# main.net
KiCad netlist of a schematic drawn in Altium Designer
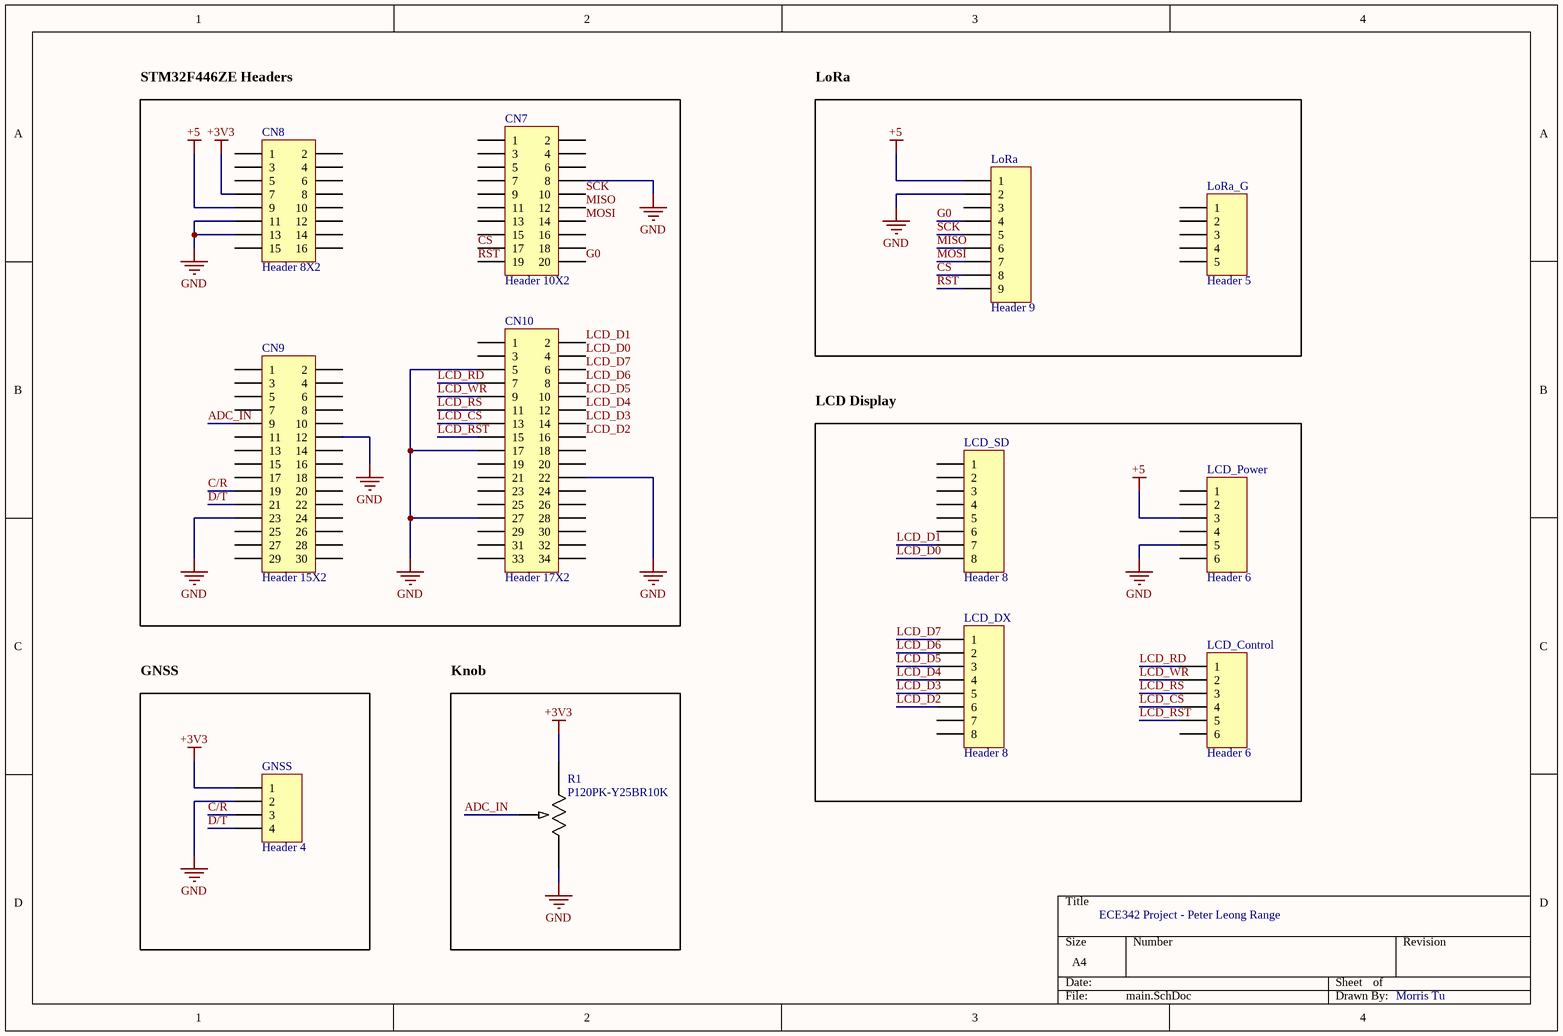
[diagram p0: main.SchDoc]

(export (version "E")
  (design (tool "Eeschema 10.0.6"))
  (components
    (comp (ref "CN7")
      (value "Header 10X2")
      (footprint "HDR2X10")
      (description "Header, 10-Pin, Dual row")
      (fields (field (name "PUBLISHER") "Altium Limited"))
      (libsource (lib "Miscellaneous Connectors") (part "Header 10X2"))
    )
    (comp (ref "CN8")
      (value "Header 8X2")
      (footprint "HDR2X8")
      (description "Header, 8-Pin, Dual row")
      (fields (field (name "PUBLISHER") "Altium Limited"))
      (libsource (lib "Miscellaneous Connectors") (part "Header 8X2"))
    )
    (comp (ref "CN9")
      (value "Header 15X2")
      (footprint "HDR2X15")
      (description "Header, 15-Pin, Dual row")
      (fields (field (name "PUBLISHER") "Altium Limited"))
      (libsource (lib "Miscellaneous Connectors") (part "Header 15X2"))
    )
    (comp (ref "CN10")
      (value "Header 17X2")
      (footprint "HDR2X17")
      (description "Header, 17-Pin, Dual row")
      (fields (field (name "PUBLISHER") "Altium Limited"))
      (libsource (lib "Miscellaneous Connectors") (part "Header 17X2"))
    )
    (comp (ref "GNSS")
      (value "Header 4")
      (footprint "HDR1X4")
      (description "Header, 4-Pin")
      (fields (field (name "PUBLISHER") "Altium Limited"))
      (libsource (lib "Miscellaneous Connectors") (part "Header 4"))
    )
    (comp (ref "LCD_Control")
      (value "Header 6")
      (footprint "HDR1X6")
      (description "Header, 6-Pin")
      (fields (field (name "PUBLISHER") "Altium Limited"))
      (libsource (lib "Miscellaneous Connectors") (part "Header 6"))
    )
    (comp (ref "LCD_DX")
      (value "Header 8")
      (footprint "HDR1X8")
      (description "Header, 8-Pin")
      (fields (field (name "PUBLISHER") "Altium Limited"))
      (libsource (lib "Miscellaneous Connectors") (part "Header 8"))
    )
    (comp (ref "LCD_Power")
      (value "Header 6")
      (footprint "HDR1X6")
      (description "Header, 6-Pin")
      (fields (field (name "PUBLISHER") "Altium Limited"))
      (libsource (lib "Miscellaneous Connectors") (part "Header 6"))
    )
    (comp (ref "LCD_SD")
      (value "Header 8")
      (footprint "HDR1X8")
      (description "Header, 8-Pin")
      (fields (field (name "PUBLISHER") "Altium Limited"))
      (libsource (lib "Miscellaneous Connectors") (part "Header 8"))
    )
    (comp (ref "LoRa")
      (value "Header 9")
      (footprint "HDR1X9")
      (description "Header, 9-Pin")
      (fields (field (name "PUBLISHER") "Altium Limited"))
      (libsource (lib "Miscellaneous Connectors") (part "Header 9"))
    )
    (comp (ref "LoRa_G")
      (value "Header 5")
      (footprint "HDR1X5")
      (description "Header, 5-Pin")
      (fields (field (name "PUBLISHER") "Altium Limited"))
      (libsource (lib "Miscellaneous Connectors") (part "Header 5"))
    )
    (comp (ref "R1")
      (value "P120PK-Y25BR10K")
      (footprint "POT_P120PK-x25_TTE")
      (description "Description")
      (fields (field (name "COPYRIGHT") "Copyright (C) 2025 Ultra Librarian. All rights reserved."))
      (libsource (lib "P120PK-Y25BR10K") (part "P120PK-Y25BR10K"))
    )
  )
  (nets
    (net (code "1") (name "+3V3") (class "Default")
      (node (ref "CN8") (pin "7") (pinfunction "7_7") (pintype "passive"))
      (node (ref "GNSS") (pin "1") (pinfunction "1_1") (pintype "passive"))
      (node (ref "R1") (pin "3") (pinfunction "3_3") (pintype "passive"))
    )
    (net (code "2") (name "+5") (class "Default")
      (node (ref "CN8") (pin "9") (pinfunction "9_9") (pintype "passive"))
      (node (ref "LCD_Power") (pin "3") (pinfunction "3_3") (pintype "passive"))
      (node (ref "LoRa") (pin "1") (pinfunction "1_1") (pintype "passive"))
    )
    (net (code "3") (name "/ADC_IN") (class "Default")
      (node (ref "CN9") (pin "9") (pinfunction "9_9") (pintype "passive"))
      (node (ref "R1") (pin "2") (pinfunction "2_2") (pintype "passive"))
    )
    (net (code "4") (name "/CS") (class "Default")
      (node (ref "CN7") (pin "17") (pinfunction "17_17") (pintype "passive"))
      (node (ref "LoRa") (pin "8") (pinfunction "8_8") (pintype "passive"))
    )
    (net (code "5") (name "/C{slash}R") (class "Default")
      (node (ref "CN9") (pin "19") (pinfunction "19_19") (pintype "passive"))
      (node (ref "GNSS") (pin "3") (pinfunction "3_3") (pintype "passive"))
    )
    (net (code "6") (name "/D{slash}T") (class "Default")
      (node (ref "CN9") (pin "21") (pinfunction "21_21") (pintype "passive"))
      (node (ref "GNSS") (pin "4") (pinfunction "4_4") (pintype "passive"))
    )
    (net (code "7") (name "/G0") (class "Default")
      (node (ref "CN7") (pin "20") (pinfunction "20_20") (pintype "passive"))
      (node (ref "LoRa") (pin "4") (pinfunction "4_4") (pintype "passive"))
    )
    (net (code "8") (name "/LCD_CS") (class "Default")
      (node (ref "CN10") (pin "13") (pinfunction "13_13") (pintype "passive"))
      (node (ref "LCD_Control") (pin "4") (pinfunction "4_4") (pintype "passive"))
    )
    (net (code "9") (name "/LCD_D0") (class "Default")
      (node (ref "CN10") (pin "4") (pinfunction "4_4") (pintype "passive"))
      (node (ref "LCD_SD") (pin "8") (pinfunction "8_8") (pintype "passive"))
    )
    (net (code "10") (name "/LCD_D1") (class "Default")
      (node (ref "CN10") (pin "2") (pinfunction "2_2") (pintype "passive"))
      (node (ref "LCD_SD") (pin "7") (pinfunction "7_7") (pintype "passive"))
    )
    (net (code "11") (name "/LCD_D2") (class "Default")
      (node (ref "CN10") (pin "16") (pinfunction "16_16") (pintype "passive"))
      (node (ref "LCD_DX") (pin "6") (pinfunction "6_6") (pintype "passive"))
    )
    (net (code "12") (name "/LCD_D3") (class "Default")
      (node (ref "CN10") (pin "14") (pinfunction "14_14") (pintype "passive"))
      (node (ref "LCD_DX") (pin "5") (pinfunction "5_5") (pintype "passive"))
    )
    (net (code "13") (name "/LCD_D4") (class "Default")
      (node (ref "CN10") (pin "12") (pinfunction "12_12") (pintype "passive"))
      (node (ref "LCD_DX") (pin "4") (pinfunction "4_4") (pintype "passive"))
    )
    (net (code "14") (name "/LCD_D5") (class "Default")
      (node (ref "CN10") (pin "10") (pinfunction "10_10") (pintype "passive"))
      (node (ref "LCD_DX") (pin "3") (pinfunction "3_3") (pintype "passive"))
    )
    (net (code "15") (name "/LCD_D6") (class "Default")
      (node (ref "CN10") (pin "8") (pinfunction "8_8") (pintype "passive"))
      (node (ref "LCD_DX") (pin "2") (pinfunction "2_2") (pintype "passive"))
    )
    (net (code "16") (name "/LCD_D7") (class "Default")
      (node (ref "CN10") (pin "6") (pinfunction "6_6") (pintype "passive"))
      (node (ref "LCD_DX") (pin "1") (pinfunction "1_1") (pintype "passive"))
    )
    (net (code "17") (name "/LCD_RD") (class "Default")
      (node (ref "CN10") (pin "7") (pinfunction "7_7") (pintype "passive"))
      (node (ref "LCD_Control") (pin "1") (pinfunction "1_1") (pintype "passive"))
    )
    (net (code "18") (name "/LCD_RS") (class "Default")
      (node (ref "CN10") (pin "11") (pinfunction "11_11") (pintype "passive"))
      (node (ref "LCD_Control") (pin "3") (pinfunction "3_3") (pintype "passive"))
    )
    (net (code "19") (name "/LCD_RST") (class "Default")
      (node (ref "CN10") (pin "15") (pinfunction "15_15") (pintype "passive"))
      (node (ref "LCD_Control") (pin "5") (pinfunction "5_5") (pintype "passive"))
    )
    (net (code "20") (name "/LCD_WR") (class "Default")
      (node (ref "CN10") (pin "9") (pinfunction "9_9") (pintype "passive"))
      (node (ref "LCD_Control") (pin "2") (pinfunction "2_2") (pintype "passive"))
    )
    (net (code "21") (name "/MISO") (class "Default")
      (node (ref "CN7") (pin "12") (pinfunction "12_12") (pintype "passive"))
      (node (ref "LoRa") (pin "6") (pinfunction "6_6") (pintype "passive"))
    )
    (net (code "22") (name "/MOSI") (class "Default")
      (node (ref "CN7") (pin "14") (pinfunction "14_14") (pintype "passive"))
      (node (ref "LoRa") (pin "7") (pinfunction "7_7") (pintype "passive"))
    )
    (net (code "23") (name "/RST") (class "Default")
      (node (ref "CN7") (pin "19") (pinfunction "19_19") (pintype "passive"))
      (node (ref "LoRa") (pin "9") (pinfunction "9_9") (pintype "passive"))
    )
    (net (code "24") (name "/SCK") (class "Default")
      (node (ref "CN7") (pin "10") (pinfunction "10_10") (pintype "passive"))
      (node (ref "LoRa") (pin "5") (pinfunction "5_5") (pintype "passive"))
    )
    (net (code "25") (name "GND") (class "Default")
      (node (ref "CN10") (pin "17") (pinfunction "17_17") (pintype "passive"))
      (node (ref "CN10") (pin "22") (pinfunction "22_22") (pintype "passive"))
      (node (ref "CN10") (pin "27") (pinfunction "27_27") (pintype "passive"))
      (node (ref "CN10") (pin "5") (pinfunction "5_5") (pintype "passive"))
      (node (ref "CN7") (pin "8") (pinfunction "8_8") (pintype "passive"))
      (node (ref "CN8") (pin "11") (pinfunction "11_11") (pintype "passive"))
      (node (ref "CN8") (pin "13") (pinfunction "13_13") (pintype "passive"))
      (node (ref "CN9") (pin "12") (pinfunction "12_12") (pintype "passive"))
      (node (ref "CN9") (pin "23") (pinfunction "23_23") (pintype "passive"))
      (node (ref "GNSS") (pin "2") (pinfunction "2_2") (pintype "passive"))
      (node (ref "LCD_Power") (pin "5") (pinfunction "5_5") (pintype "passive"))
      (node (ref "LoRa") (pin "2") (pinfunction "2_2") (pintype "passive"))
      (node (ref "R1") (pin "1") (pinfunction "1_1") (pintype "passive"))
    )
    (net (code "26") (name "unconnected-(CN7-Pad1)") (class "Default")
      (node (ref "CN7") (pin "1") (pinfunction "1_1") (pintype "passive"))
    )
    (net (code "27") (name "unconnected-(CN7-Pad2)") (class "Default")
      (node (ref "CN7") (pin "2") (pinfunction "2_2") (pintype "passive"))
    )
    (net (code "28") (name "unconnected-(CN7-Pad3)") (class "Default")
      (node (ref "CN7") (pin "3") (pinfunction "3_3") (pintype "passive"))
    )
    (net (code "29") (name "unconnected-(CN7-Pad4)") (class "Default")
      (node (ref "CN7") (pin "4") (pinfunction "4_4") (pintype "passive"))
    )
    (net (code "30") (name "unconnected-(CN7-Pad5)") (class "Default")
      (node (ref "CN7") (pin "5") (pinfunction "5_5") (pintype "passive"))
    )
    (net (code "31") (name "unconnected-(CN7-Pad6)") (class "Default")
      (node (ref "CN7") (pin "6") (pinfunction "6_6") (pintype "passive"))
    )
    (net (code "32") (name "unconnected-(CN7-Pad7)") (class "Default")
      (node (ref "CN7") (pin "7") (pinfunction "7_7") (pintype "passive"))
    )
    (net (code "33") (name "unconnected-(CN7-Pad9)") (class "Default")
      (node (ref "CN7") (pin "9") (pinfunction "9_9") (pintype "passive"))
    )
    (net (code "34") (name "unconnected-(CN7-Pad11)") (class "Default")
      (node (ref "CN7") (pin "11") (pinfunction "11_11") (pintype "passive"))
    )
    (net (code "35") (name "unconnected-(CN7-Pad13)") (class "Default")
      (node (ref "CN7") (pin "13") (pinfunction "13_13") (pintype "passive"))
    )
    (net (code "36") (name "unconnected-(CN7-Pad15)") (class "Default")
      (node (ref "CN7") (pin "15") (pinfunction "15_15") (pintype "passive"))
    )
    (net (code "37") (name "unconnected-(CN7-Pad16)") (class "Default")
      (node (ref "CN7") (pin "16") (pinfunction "16_16") (pintype "passive"))
    )
    (net (code "38") (name "unconnected-(CN7-Pad18)") (class "Default")
      (node (ref "CN7") (pin "18") (pinfunction "18_18") (pintype "passive"))
    )
    (net (code "39") (name "unconnected-(CN8-Pad1)") (class "Default")
      (node (ref "CN8") (pin "1") (pinfunction "1_1") (pintype "passive"))
    )
    (net (code "40") (name "unconnected-(CN8-Pad2)") (class "Default")
      (node (ref "CN8") (pin "2") (pinfunction "2_2") (pintype "passive"))
    )
    (net (code "41") (name "unconnected-(CN8-Pad3)") (class "Default")
      (node (ref "CN8") (pin "3") (pinfunction "3_3") (pintype "passive"))
    )
    (net (code "42") (name "unconnected-(CN8-Pad4)") (class "Default")
      (node (ref "CN8") (pin "4") (pinfunction "4_4") (pintype "passive"))
    )
    (net (code "43") (name "unconnected-(CN8-Pad5)") (class "Default")
      (node (ref "CN8") (pin "5") (pinfunction "5_5") (pintype "passive"))
    )
    (net (code "44") (name "unconnected-(CN8-Pad6)") (class "Default")
      (node (ref "CN8") (pin "6") (pinfunction "6_6") (pintype "passive"))
    )
    (net (code "45") (name "unconnected-(CN8-Pad8)") (class "Default")
      (node (ref "CN8") (pin "8") (pinfunction "8_8") (pintype "passive"))
    )
    (net (code "46") (name "unconnected-(CN8-Pad10)") (class "Default")
      (node (ref "CN8") (pin "10") (pinfunction "10_10") (pintype "passive"))
    )
    (net (code "47") (name "unconnected-(CN8-Pad12)") (class "Default")
      (node (ref "CN8") (pin "12") (pinfunction "12_12") (pintype "passive"))
    )
    (net (code "48") (name "unconnected-(CN8-Pad14)") (class "Default")
      (node (ref "CN8") (pin "14") (pinfunction "14_14") (pintype "passive"))
    )
    (net (code "49") (name "unconnected-(CN8-Pad15)") (class "Default")
      (node (ref "CN8") (pin "15") (pinfunction "15_15") (pintype "passive"))
    )
    (net (code "50") (name "unconnected-(CN8-Pad16)") (class "Default")
      (node (ref "CN8") (pin "16") (pinfunction "16_16") (pintype "passive"))
    )
    (net (code "51") (name "unconnected-(CN9-Pad1)") (class "Default")
      (node (ref "CN9") (pin "1") (pinfunction "1_1") (pintype "passive"))
    )
    (net (code "52") (name "unconnected-(CN9-Pad2)") (class "Default")
      (node (ref "CN9") (pin "2") (pinfunction "2_2") (pintype "passive"))
    )
    (net (code "53") (name "unconnected-(CN9-Pad3)") (class "Default")
      (node (ref "CN9") (pin "3") (pinfunction "3_3") (pintype "passive"))
    )
    (net (code "54") (name "unconnected-(CN9-Pad4)") (class "Default")
      (node (ref "CN9") (pin "4") (pinfunction "4_4") (pintype "passive"))
    )
    (net (code "55") (name "unconnected-(CN9-Pad5)") (class "Default")
      (node (ref "CN9") (pin "5") (pinfunction "5_5") (pintype "passive"))
    )
    (net (code "56") (name "unconnected-(CN9-Pad6)") (class "Default")
      (node (ref "CN9") (pin "6") (pinfunction "6_6") (pintype "passive"))
    )
    (net (code "57") (name "unconnected-(CN9-Pad7)") (class "Default")
      (node (ref "CN9") (pin "7") (pinfunction "7_7") (pintype "passive"))
    )
    (net (code "58") (name "unconnected-(CN9-Pad8)") (class "Default")
      (node (ref "CN9") (pin "8") (pinfunction "8_8") (pintype "passive"))
    )
    (net (code "59") (name "unconnected-(CN9-Pad10)") (class "Default")
      (node (ref "CN9") (pin "10") (pinfunction "10_10") (pintype "passive"))
    )
    (net (code "60") (name "unconnected-(CN9-Pad11)") (class "Default")
      (node (ref "CN9") (pin "11") (pinfunction "11_11") (pintype "passive"))
    )
    (net (code "61") (name "unconnected-(CN9-Pad13)") (class "Default")
      (node (ref "CN9") (pin "13") (pinfunction "13_13") (pintype "passive"))
    )
    (net (code "62") (name "unconnected-(CN9-Pad14)") (class "Default")
      (node (ref "CN9") (pin "14") (pinfunction "14_14") (pintype "passive"))
    )
    (net (code "63") (name "unconnected-(CN9-Pad15)") (class "Default")
      (node (ref "CN9") (pin "15") (pinfunction "15_15") (pintype "passive"))
    )
    (net (code "64") (name "unconnected-(CN9-Pad16)") (class "Default")
      (node (ref "CN9") (pin "16") (pinfunction "16_16") (pintype "passive"))
    )
    (net (code "65") (name "unconnected-(CN9-Pad17)") (class "Default")
      (node (ref "CN9") (pin "17") (pinfunction "17_17") (pintype "passive"))
    )
    (net (code "66") (name "unconnected-(CN9-Pad18)") (class "Default")
      (node (ref "CN9") (pin "18") (pinfunction "18_18") (pintype "passive"))
    )
    (net (code "67") (name "unconnected-(CN9-Pad20)") (class "Default")
      (node (ref "CN9") (pin "20") (pinfunction "20_20") (pintype "passive"))
    )
    (net (code "68") (name "unconnected-(CN9-Pad22)") (class "Default")
      (node (ref "CN9") (pin "22") (pinfunction "22_22") (pintype "passive"))
    )
    (net (code "69") (name "unconnected-(CN9-Pad24)") (class "Default")
      (node (ref "CN9") (pin "24") (pinfunction "24_24") (pintype "passive"))
    )
    (net (code "70") (name "unconnected-(CN9-Pad25)") (class "Default")
      (node (ref "CN9") (pin "25") (pinfunction "25_25") (pintype "passive"))
    )
    (net (code "71") (name "unconnected-(CN9-Pad26)") (class "Default")
      (node (ref "CN9") (pin "26") (pinfunction "26_26") (pintype "passive"))
    )
    (net (code "72") (name "unconnected-(CN9-Pad27)") (class "Default")
      (node (ref "CN9") (pin "27") (pinfunction "27_27") (pintype "passive"))
    )
    (net (code "73") (name "unconnected-(CN9-Pad28)") (class "Default")
      (node (ref "CN9") (pin "28") (pinfunction "28_28") (pintype "passive"))
    )
    (net (code "74") (name "unconnected-(CN9-Pad29)") (class "Default")
      (node (ref "CN9") (pin "29") (pinfunction "29_29") (pintype "passive"))
    )
    (net (code "75") (name "unconnected-(CN9-Pad30)") (class "Default")
      (node (ref "CN9") (pin "30") (pinfunction "30_30") (pintype "passive"))
    )
    (net (code "76") (name "unconnected-(CN10-Pad1)") (class "Default")
      (node (ref "CN10") (pin "1") (pinfunction "1_1") (pintype "passive"))
    )
    (net (code "77") (name "unconnected-(CN10-Pad3)") (class "Default")
      (node (ref "CN10") (pin "3") (pinfunction "3_3") (pintype "passive"))
    )
    (net (code "78") (name "unconnected-(CN10-Pad18)") (class "Default")
      (node (ref "CN10") (pin "18") (pinfunction "18_18") (pintype "passive"))
    )
    (net (code "79") (name "unconnected-(CN10-Pad19)") (class "Default")
      (node (ref "CN10") (pin "19") (pinfunction "19_19") (pintype "passive"))
    )
    (net (code "80") (name "unconnected-(CN10-Pad20)") (class "Default")
      (node (ref "CN10") (pin "20") (pinfunction "20_20") (pintype "passive"))
    )
    (net (code "81") (name "unconnected-(CN10-Pad21)") (class "Default")
      (node (ref "CN10") (pin "21") (pinfunction "21_21") (pintype "passive"))
    )
    (net (code "82") (name "unconnected-(CN10-Pad23)") (class "Default")
      (node (ref "CN10") (pin "23") (pinfunction "23_23") (pintype "passive"))
    )
    (net (code "83") (name "unconnected-(CN10-Pad24)") (class "Default")
      (node (ref "CN10") (pin "24") (pinfunction "24_24") (pintype "passive"))
    )
    (net (code "84") (name "unconnected-(CN10-Pad25)") (class "Default")
      (node (ref "CN10") (pin "25") (pinfunction "25_25") (pintype "passive"))
    )
    (net (code "85") (name "unconnected-(CN10-Pad26)") (class "Default")
      (node (ref "CN10") (pin "26") (pinfunction "26_26") (pintype "passive"))
    )
    (net (code "86") (name "unconnected-(CN10-Pad28)") (class "Default")
      (node (ref "CN10") (pin "28") (pinfunction "28_28") (pintype "passive"))
    )
    (net (code "87") (name "unconnected-(CN10-Pad29)") (class "Default")
      (node (ref "CN10") (pin "29") (pinfunction "29_29") (pintype "passive"))
    )
    (net (code "88") (name "unconnected-(CN10-Pad30)") (class "Default")
      (node (ref "CN10") (pin "30") (pinfunction "30_30") (pintype "passive"))
    )
    (net (code "89") (name "unconnected-(CN10-Pad31)") (class "Default")
      (node (ref "CN10") (pin "31") (pinfunction "31_31") (pintype "passive"))
    )
    (net (code "90") (name "unconnected-(CN10-Pad32)") (class "Default")
      (node (ref "CN10") (pin "32") (pinfunction "32_32") (pintype "passive"))
    )
    (net (code "91") (name "unconnected-(CN10-Pad33)") (class "Default")
      (node (ref "CN10") (pin "33") (pinfunction "33_33") (pintype "passive"))
    )
    (net (code "92") (name "unconnected-(CN10-Pad34)") (class "Default")
      (node (ref "CN10") (pin "34") (pinfunction "34_34") (pintype "passive"))
    )
    (net (code "93") (name "unconnected-(LCD_Control-Pad6)") (class "Default")
      (node (ref "LCD_Control") (pin "6") (pinfunction "6_6") (pintype "passive"))
    )
    (net (code "94") (name "unconnected-(LCD_DX-Pad7)") (class "Default")
      (node (ref "LCD_DX") (pin "7") (pinfunction "7_7") (pintype "passive"))
    )
    (net (code "95") (name "unconnected-(LCD_DX-Pad8)") (class "Default")
      (node (ref "LCD_DX") (pin "8") (pinfunction "8_8") (pintype "passive"))
    )
    (net (code "96") (name "unconnected-(LCD_Power-Pad1)") (class "Default")
      (node (ref "LCD_Power") (pin "1") (pinfunction "1_1") (pintype "passive"))
    )
    (net (code "97") (name "unconnected-(LCD_Power-Pad2)") (class "Default")
      (node (ref "LCD_Power") (pin "2") (pinfunction "2_2") (pintype "passive"))
    )
    (net (code "98") (name "unconnected-(LCD_Power-Pad4)") (class "Default")
      (node (ref "LCD_Power") (pin "4") (pinfunction "4_4") (pintype "passive"))
    )
    (net (code "99") (name "unconnected-(LCD_Power-Pad6)") (class "Default")
      (node (ref "LCD_Power") (pin "6") (pinfunction "6_6") (pintype "passive"))
    )
    (net (code "100") (name "unconnected-(LCD_SD-Pad1)") (class "Default")
      (node (ref "LCD_SD") (pin "1") (pinfunction "1_1") (pintype "passive"))
    )
    (net (code "101") (name "unconnected-(LCD_SD-Pad2)") (class "Default")
      (node (ref "LCD_SD") (pin "2") (pinfunction "2_2") (pintype "passive"))
    )
    (net (code "102") (name "unconnected-(LCD_SD-Pad3)") (class "Default")
      (node (ref "LCD_SD") (pin "3") (pinfunction "3_3") (pintype "passive"))
    )
    (net (code "103") (name "unconnected-(LCD_SD-Pad4)") (class "Default")
      (node (ref "LCD_SD") (pin "4") (pinfunction "4_4") (pintype "passive"))
    )
    (net (code "104") (name "unconnected-(LCD_SD-Pad5)") (class "Default")
      (node (ref "LCD_SD") (pin "5") (pinfunction "5_5") (pintype "passive"))
    )
    (net (code "105") (name "unconnected-(LCD_SD-Pad6)") (class "Default")
      (node (ref "LCD_SD") (pin "6") (pinfunction "6_6") (pintype "passive"))
    )
    (net (code "106") (name "unconnected-(LoRa-Pad3)") (class "Default")
      (node (ref "LoRa") (pin "3") (pinfunction "3_3") (pintype "passive"))
    )
    (net (code "107") (name "unconnected-(LoRa_G-Pad1)") (class "Default")
      (node (ref "LoRa_G") (pin "1") (pinfunction "1_1") (pintype "passive"))
    )
    (net (code "108") (name "unconnected-(LoRa_G-Pad2)") (class "Default")
      (node (ref "LoRa_G") (pin "2") (pinfunction "2_2") (pintype "passive"))
    )
    (net (code "109") (name "unconnected-(LoRa_G-Pad3)") (class "Default")
      (node (ref "LoRa_G") (pin "3") (pinfunction "3_3") (pintype "passive"))
    )
    (net (code "110") (name "unconnected-(LoRa_G-Pad4)") (class "Default")
      (node (ref "LoRa_G") (pin "4") (pinfunction "4_4") (pintype "passive"))
    )
    (net (code "111") (name "unconnected-(LoRa_G-Pad5)") (class "Default")
      (node (ref "LoRa_G") (pin "5") (pinfunction "5_5") (pintype "passive"))
    )
  )
)
